# GR_Pi.net
KiCad netlist of a schematic drawn in Altium Designer
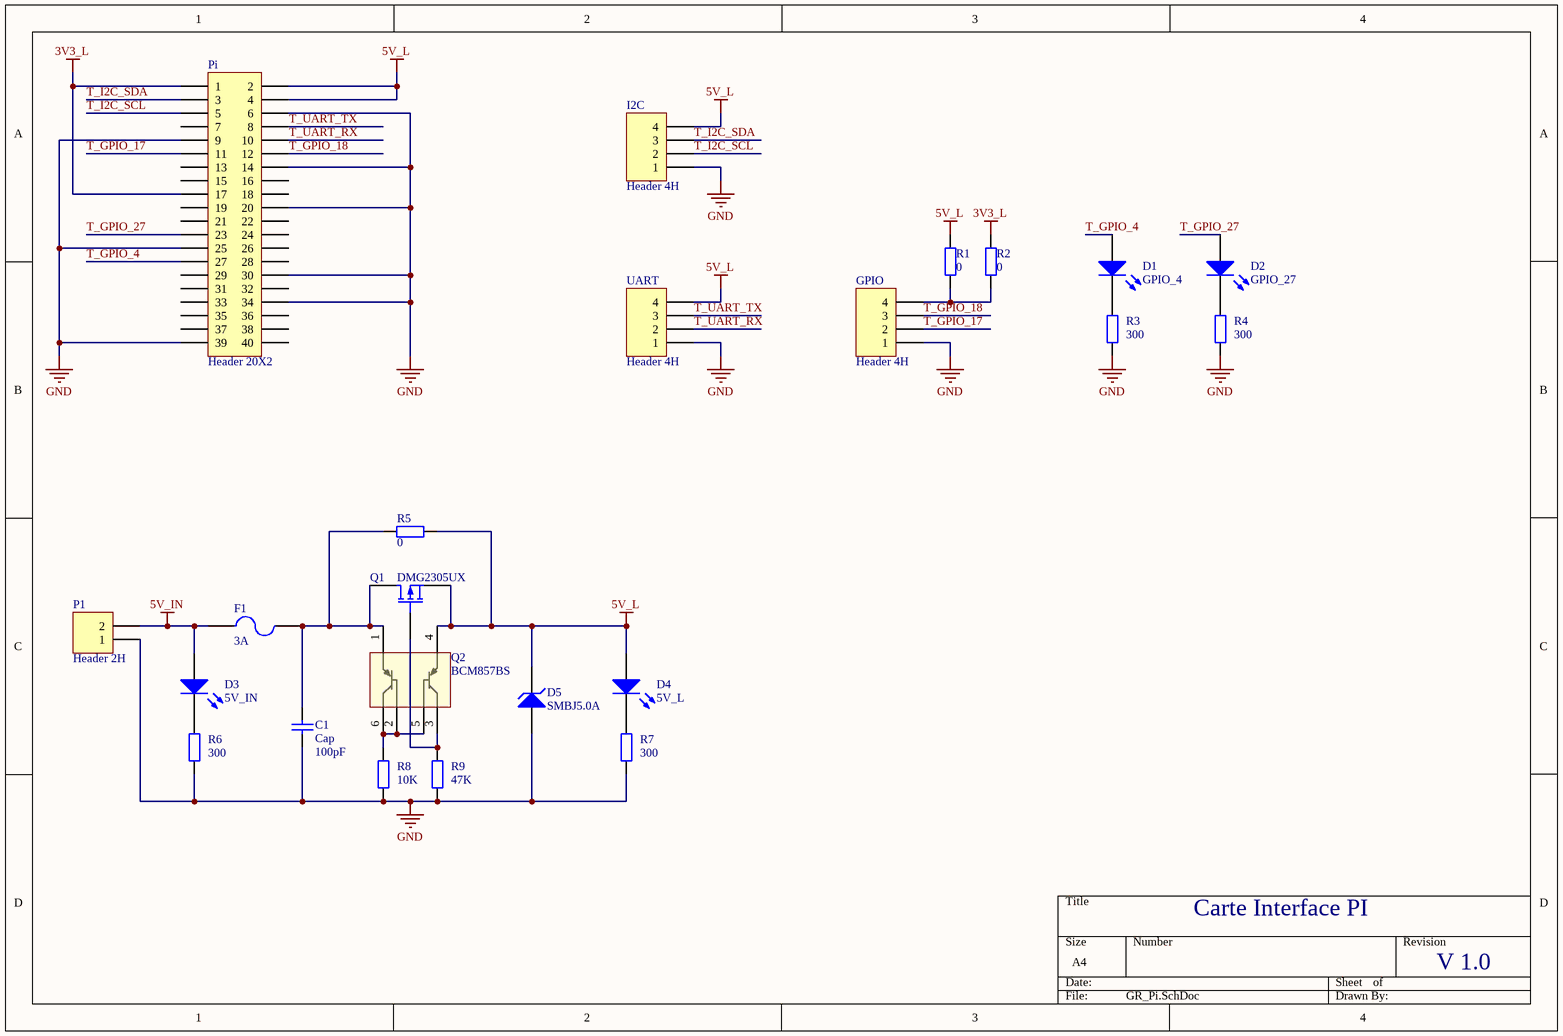
[diagram p0: GR_Pi.SchDoc]

(export (version "E")
  (design (tool "Eeschema 10.0.6"))
  (components
    (comp (ref "C1")
      (value "Cap")
      (footprint "Capacitor 1206")
      (description "Capacitor")
      (fields (field (name "ALTIUM_VALUE") "100pF") (field (name "PUBLISHER") "Altium Limited"))
      (libsource (lib "Miscellaneous Devices") (part "Cap"))
    )
    (comp (ref "D1")
      (value "GPIO_4")
      (footprint "KP-3216SEC")
      (description "Typical RED, GREEN, YELLOW, AMBER GaAs LED")
      (fields (field (name "PUBLISHER") "Altium Limited"))
      (libsource (lib "Miscellaneous Devices") (part "LED2"))
    )
    (comp (ref "D2")
      (value "GPIO_27")
      (footprint "KP-3216SEC")
      (description "Typical RED, GREEN, YELLOW, AMBER GaAs LED")
      (fields (field (name "PUBLISHER") "Altium Limited"))
      (libsource (lib "Miscellaneous Devices") (part "LED2"))
    )
    (comp (ref "D3")
      (value "5V_IN")
      (footprint "KP-3216SEC")
      (description "Typical RED, GREEN, YELLOW, AMBER GaAs LED")
      (fields (field (name "PUBLISHER") "Altium Limited"))
      (libsource (lib "Miscellaneous Devices") (part "LED2"))
    )
    (comp (ref "D4")
      (value "5V_L")
      (footprint "KP-3216SEC")
      (description "Typical RED, GREEN, YELLOW, AMBER GaAs LED")
      (fields (field (name "PUBLISHER") "Altium Limited"))
      (libsource (lib "Miscellaneous Devices") (part "LED2"))
    )
    (comp (ref "D5")
      (value "SMBJ5.0A")
      (footprint "SMB")
      (description "Zener Diode")
      (fields (field (name "PUBLISHER") "Altium Limited"))
      (libsource (lib "Miscellaneous Devices") (part "D Zener"))
    )
    (comp (ref "F1")
      (value "3A")
      (footprint "Resistor 1206")
      (description "Fuse")
      (fields (field (name "PUBLISHER") "Altium Limited"))
      (libsource (lib "Miscellaneous Devices") (part "Fuse 2"))
    )
    (comp (ref "GPIO")
      (value "Header 4H")
      (footprint "S4B-XH-A")
      (description "Header, 4-Pin, Right Angle")
      (fields (field (name "PUBLISHER") "Altium Limited"))
      (libsource (lib "Miscellaneous Connectors") (part "Header 4H"))
    )
    (comp (ref "I2C")
      (value "Header 4H")
      (footprint "S4B-XH-A")
      (description "Header, 4-Pin, Right Angle")
      (fields (field (name "PUBLISHER") "Altium Limited"))
      (libsource (lib "Miscellaneous Connectors") (part "Header 4H"))
    )
    (comp (ref "P1")
      (value "Header 2H")
      (footprint "Molex_MiniFitJr_2x1H")
      (description "Header, 2-Pin, Right Angle")
      (fields (field (name "PUBLISHER") "Altium Limited"))
      (libsource (lib "Miscellaneous Connectors") (part "Header 2H"))
    )
    (comp (ref "Pi")
      (value "Header 20X2")
      (footprint "HDR2X20")
      (description "Header, 20-Pin, Dual row")
      (fields (field (name "PUBLISHER") "Altium Limited"))
      (libsource (lib "Miscellaneous Connectors") (part "Header 20X2"))
    )
    (comp (ref "Q1")
      (value "DMG2305UX")
      (footprint "SOT23_L")
      (description "P-Channel MOSFET")
      (fields (field (name "PUBLISHER") "Altium Limited"))
      (libsource (lib "Miscellaneous Devices") (part "MOSFET-P"))
    )
    (comp (ref "Q2")
      (value "BCM857BS")
      (footprint "SamacSys:SOT65P210X110-6N")
      (description "Transistor")
      (libsource (lib "SamacSys") (part "BCM857BS"))
    )
    (comp (ref "R1")
      (value "0")
      (footprint "Resistor 1206")
      (description "Resistor")
      (fields (field (name "Comment") "Res2") (field (name "PUBLISHER") "Altium Limited"))
      (libsource (lib "") (part "Res2_2"))
    )
    (comp (ref "R2")
      (value "0")
      (footprint "Resistor 1206")
      (description "Resistor")
      (fields (field (name "Comment") "Res2") (field (name "PUBLISHER") "Altium Limited"))
      (libsource (lib "") (part "Res2_2"))
    )
    (comp (ref "R3")
      (value "300")
      (footprint "Resistor 1206")
      (description "Resistor")
      (fields (field (name "Comment") "Res2") (field (name "PUBLISHER") "Altium Limited"))
      (libsource (lib "Miscellaneous Devices") (part "Res2"))
    )
    (comp (ref "R4")
      (value "300")
      (footprint "Resistor 1206")
      (description "Resistor")
      (fields (field (name "Comment") "Res2") (field (name "PUBLISHER") "Altium Limited"))
      (libsource (lib "Miscellaneous Devices") (part "Res2"))
    )
    (comp (ref "R5")
      (value "0")
      (footprint "Resistor 1206")
      (description "Resistor")
      (fields (field (name "Comment") "Res2") (field (name "PUBLISHER") "Altium Limited"))
      (libsource (lib "") (part "Res2_1"))
    )
    (comp (ref "R6")
      (value "300")
      (footprint "Resistor 1206")
      (description "Resistor")
      (fields (field (name "Comment") "Res2") (field (name "PUBLISHER") "Altium Limited"))
      (libsource (lib "Miscellaneous Devices") (part "Res2"))
    )
    (comp (ref "R7")
      (value "300")
      (footprint "Resistor 1206")
      (description "Resistor")
      (fields (field (name "Comment") "Res2") (field (name "PUBLISHER") "Altium Limited"))
      (libsource (lib "Miscellaneous Devices") (part "Res2"))
    )
    (comp (ref "R8")
      (value "10K")
      (footprint "Resistor 1206")
      (description "Resistor")
      (fields (field (name "Comment") "Res2") (field (name "PUBLISHER") "Altium Limited"))
      (libsource (lib "Miscellaneous Devices") (part "Res2"))
    )
    (comp (ref "R9")
      (value "47K")
      (footprint "Resistor 1206")
      (description "Resistor")
      (fields (field (name "Comment") "Res2") (field (name "PUBLISHER") "Altium Limited"))
      (libsource (lib "Miscellaneous Devices") (part "Res2"))
    )
    (comp (ref "UART")
      (value "Header 4H")
      (footprint "S4B-XH-A")
      (description "Header, 4-Pin, Right Angle")
      (fields (field (name "PUBLISHER") "Altium Limited"))
      (libsource (lib "Miscellaneous Connectors") (part "Header 4H"))
    )
  )
  (nets
    (net (code "1") (name "/T_GPIO_4") (class "Default")
      (node (ref "D1") (pin "1") (pinfunction "A_1") (pintype "passive"))
      (node (ref "Pi") (pin "27") (pinfunction "27_27") (pintype "passive"))
    )
    (net (code "2") (name "/T_GPIO_17") (class "Default")
      (node (ref "GPIO") (pin "2") (pinfunction "2_2") (pintype "passive"))
      (node (ref "Pi") (pin "11") (pinfunction "11_11") (pintype "passive"))
    )
    (net (code "3") (name "/T_GPIO_18") (class "Default")
      (node (ref "GPIO") (pin "3") (pinfunction "3_3") (pintype "passive"))
      (node (ref "Pi") (pin "12") (pinfunction "12_12") (pintype "passive"))
    )
    (net (code "4") (name "/T_GPIO_27") (class "Default")
      (node (ref "D2") (pin "1") (pinfunction "A_1") (pintype "passive"))
      (node (ref "Pi") (pin "23") (pinfunction "23_23") (pintype "passive"))
    )
    (net (code "5") (name "/T_I2C_SCL") (class "Default")
      (node (ref "I2C") (pin "2") (pinfunction "2_2") (pintype "passive"))
      (node (ref "Pi") (pin "5") (pinfunction "5_5") (pintype "passive"))
    )
    (net (code "6") (name "/T_I2C_SDA") (class "Default")
      (node (ref "I2C") (pin "3") (pinfunction "3_3") (pintype "passive"))
      (node (ref "Pi") (pin "3") (pinfunction "3_3") (pintype "passive"))
    )
    (net (code "7") (name "/T_UART_RX") (class "Default")
      (node (ref "Pi") (pin "10") (pinfunction "10_10") (pintype "passive"))
      (node (ref "UART") (pin "2") (pinfunction "2_2") (pintype "passive"))
    )
    (net (code "8") (name "/T_UART_TX") (class "Default")
      (node (ref "Pi") (pin "8") (pinfunction "8_8") (pintype "passive"))
      (node (ref "UART") (pin "3") (pinfunction "3_3") (pintype "passive"))
    )
    (net (code "9") (name "3V3_L") (class "Default")
      (node (ref "Pi") (pin "1") (pinfunction "1_1") (pintype "passive"))
      (node (ref "Pi") (pin "17") (pinfunction "17_17") (pintype "passive"))
      (node (ref "R2") (pin "1") (pinfunction "1_1") (pintype "passive"))
    )
    (net (code "10") (name "5V_IN") (class "Default")
      (node (ref "D3") (pin "1") (pinfunction "A_1") (pintype "passive"))
      (node (ref "F1") (pin "1") (pinfunction "1_1") (pintype "passive"))
      (node (ref "P1") (pin "2") (pinfunction "2_2") (pintype "passive"))
    )
    (net (code "11") (name "5V_L") (class "Default")
      (node (ref "D4") (pin "1") (pinfunction "A_1") (pintype "passive"))
      (node (ref "D5") (pin "2") (pinfunction "K_2") (pintype "passive"))
      (node (ref "I2C") (pin "4") (pinfunction "4_4") (pintype "passive"))
      (node (ref "Pi") (pin "2") (pinfunction "2_2") (pintype "passive"))
      (node (ref "Pi") (pin "4") (pinfunction "4_4") (pintype "passive"))
      (node (ref "Q1") (pin "3") (pinfunction "S_3") (pintype "passive"))
      (node (ref "Q2") (pin "4") (pinfunction "EMITTER_TR2_4") (pintype "passive"))
      (node (ref "R1") (pin "1") (pinfunction "1_1") (pintype "passive"))
      (node (ref "R5") (pin "1") (pinfunction "1_1") (pintype "passive"))
      (node (ref "UART") (pin "4") (pinfunction "4_4") (pintype "passive"))
    )
    (net (code "12") (name "GND") (class "Default")
      (node (ref "C1") (pin "1") (pinfunction "1_1") (pintype "passive"))
      (node (ref "D5") (pin "1") (pinfunction "A_1") (pintype "passive"))
      (node (ref "GPIO") (pin "1") (pinfunction "1_1") (pintype "passive"))
      (node (ref "I2C") (pin "1") (pinfunction "1_1") (pintype "passive"))
      (node (ref "P1") (pin "1") (pinfunction "1_1") (pintype "passive"))
      (node (ref "Pi") (pin "14") (pinfunction "14_14") (pintype "passive"))
      (node (ref "Pi") (pin "20") (pinfunction "20_20") (pintype "passive"))
      (node (ref "Pi") (pin "25") (pinfunction "25_25") (pintype "passive"))
      (node (ref "Pi") (pin "30") (pinfunction "30_30") (pintype "passive"))
      (node (ref "Pi") (pin "34") (pinfunction "34_34") (pintype "passive"))
      (node (ref "Pi") (pin "39") (pinfunction "39_39") (pintype "passive"))
      (node (ref "Pi") (pin "6") (pinfunction "6_6") (pintype "passive"))
      (node (ref "Pi") (pin "9") (pinfunction "9_9") (pintype "passive"))
      (node (ref "R3") (pin "1") (pinfunction "1_1") (pintype "passive"))
      (node (ref "R4") (pin "1") (pinfunction "1_1") (pintype "passive"))
      (node (ref "R6") (pin "1") (pinfunction "1_1") (pintype "passive"))
      (node (ref "R7") (pin "1") (pinfunction "1_1") (pintype "passive"))
      (node (ref "R8") (pin "1") (pinfunction "1_1") (pintype "passive"))
      (node (ref "R9") (pin "1") (pinfunction "1_1") (pintype "passive"))
      (node (ref "UART") (pin "1") (pinfunction "1_1") (pintype "passive"))
    )
    (net (code "13") (name "Net-(D1-K)") (class "Default")
      (node (ref "D1") (pin "2") (pinfunction "K_2") (pintype "passive"))
      (node (ref "R3") (pin "2") (pinfunction "2_2") (pintype "passive"))
    )
    (net (code "14") (name "Net-(D2-K)") (class "Default")
      (node (ref "D2") (pin "2") (pinfunction "K_2") (pintype "passive"))
      (node (ref "R4") (pin "2") (pinfunction "2_2") (pintype "passive"))
    )
    (net (code "15") (name "Net-(D3-K)") (class "Default")
      (node (ref "D3") (pin "2") (pinfunction "K_2") (pintype "passive"))
      (node (ref "R6") (pin "2") (pinfunction "2_2") (pintype "passive"))
    )
    (net (code "16") (name "Net-(D4-K)") (class "Default")
      (node (ref "D4") (pin "2") (pinfunction "K_2") (pintype "passive"))
      (node (ref "R7") (pin "2") (pinfunction "2_2") (pintype "passive"))
    )
    (net (code "17") (name "Net-(GPIO-Pad4)") (class "Default")
      (node (ref "GPIO") (pin "4") (pinfunction "4_4") (pintype "passive"))
      (node (ref "R1") (pin "2") (pinfunction "2_2") (pintype "passive"))
      (node (ref "R2") (pin "2") (pinfunction "2_2") (pintype "passive"))
    )
    (net (code "18") (name "Net-(Q1-D)") (class "Default")
      (node (ref "C1") (pin "2") (pinfunction "2_2") (pintype "passive"))
      (node (ref "F1") (pin "2") (pinfunction "2_2") (pintype "passive"))
      (node (ref "Q1") (pin "1") (pinfunction "D_1") (pintype "passive"))
      (node (ref "Q2") (pin "1") (pinfunction "EMITTER_TR1_1") (pintype "passive"))
      (node (ref "R5") (pin "2") (pinfunction "2_2") (pintype "passive"))
    )
    (net (code "19") (name "Net-(Q1-G)") (class "Default")
      (node (ref "Q1") (pin "2") (pinfunction "G_2") (pintype "passive"))
      (node (ref "Q2") (pin "3") (pinfunction "COLLECTOR_TR2_3") (pintype "passive"))
      (node (ref "R9") (pin "2") (pinfunction "2_2") (pintype "passive"))
    )
    (net (code "20") (name "Net-(Q2-BASE_TR1)") (class "Default")
      (node (ref "Q2") (pin "2") (pinfunction "BASE_TR1_2") (pintype "passive"))
      (node (ref "Q2") (pin "5") (pinfunction "BASE_TR2_5") (pintype "passive"))
      (node (ref "Q2") (pin "6") (pinfunction "COLLECTOR_TR1_6") (pintype "passive"))
      (node (ref "R8") (pin "2") (pinfunction "2_2") (pintype "passive"))
    )
    (net (code "21") (name "unconnected-(Pi-Pad7)") (class "Default")
      (node (ref "Pi") (pin "7") (pinfunction "7_7") (pintype "passive"))
    )
    (net (code "22") (name "unconnected-(Pi-Pad13)") (class "Default")
      (node (ref "Pi") (pin "13") (pinfunction "13_13") (pintype "passive"))
    )
    (net (code "23") (name "unconnected-(Pi-Pad15)") (class "Default")
      (node (ref "Pi") (pin "15") (pinfunction "15_15") (pintype "passive"))
    )
    (net (code "24") (name "unconnected-(Pi-Pad16)") (class "Default")
      (node (ref "Pi") (pin "16") (pinfunction "16_16") (pintype "passive"))
    )
    (net (code "25") (name "unconnected-(Pi-Pad18)") (class "Default")
      (node (ref "Pi") (pin "18") (pinfunction "18_18") (pintype "passive"))
    )
    (net (code "26") (name "unconnected-(Pi-Pad19)") (class "Default")
      (node (ref "Pi") (pin "19") (pinfunction "19_19") (pintype "passive"))
    )
    (net (code "27") (name "unconnected-(Pi-Pad21)") (class "Default")
      (node (ref "Pi") (pin "21") (pinfunction "21_21") (pintype "passive"))
    )
    (net (code "28") (name "unconnected-(Pi-Pad22)") (class "Default")
      (node (ref "Pi") (pin "22") (pinfunction "22_22") (pintype "passive"))
    )
    (net (code "29") (name "unconnected-(Pi-Pad24)") (class "Default")
      (node (ref "Pi") (pin "24") (pinfunction "24_24") (pintype "passive"))
    )
    (net (code "30") (name "unconnected-(Pi-Pad26)") (class "Default")
      (node (ref "Pi") (pin "26") (pinfunction "26_26") (pintype "passive"))
    )
    (net (code "31") (name "unconnected-(Pi-Pad28)") (class "Default")
      (node (ref "Pi") (pin "28") (pinfunction "28_28") (pintype "passive"))
    )
    (net (code "32") (name "unconnected-(Pi-Pad29)") (class "Default")
      (node (ref "Pi") (pin "29") (pinfunction "29_29") (pintype "passive"))
    )
    (net (code "33") (name "unconnected-(Pi-Pad31)") (class "Default")
      (node (ref "Pi") (pin "31") (pinfunction "31_31") (pintype "passive"))
    )
    (net (code "34") (name "unconnected-(Pi-Pad32)") (class "Default")
      (node (ref "Pi") (pin "32") (pinfunction "32_32") (pintype "passive"))
    )
    (net (code "35") (name "unconnected-(Pi-Pad33)") (class "Default")
      (node (ref "Pi") (pin "33") (pinfunction "33_33") (pintype "passive"))
    )
    (net (code "36") (name "unconnected-(Pi-Pad35)") (class "Default")
      (node (ref "Pi") (pin "35") (pinfunction "35_35") (pintype "passive"))
    )
    (net (code "37") (name "unconnected-(Pi-Pad36)") (class "Default")
      (node (ref "Pi") (pin "36") (pinfunction "36_36") (pintype "passive"))
    )
    (net (code "38") (name "unconnected-(Pi-Pad37)") (class "Default")
      (node (ref "Pi") (pin "37") (pinfunction "37_37") (pintype "passive"))
    )
    (net (code "39") (name "unconnected-(Pi-Pad38)") (class "Default")
      (node (ref "Pi") (pin "38") (pinfunction "38_38") (pintype "passive"))
    )
    (net (code "40") (name "unconnected-(Pi-Pad40)") (class "Default")
      (node (ref "Pi") (pin "40") (pinfunction "40_40") (pintype "passive"))
    )
  )
)
